# 250100020129x-HW-V3_0.net
KiCad netlist of a schematic drawn in EAGLE
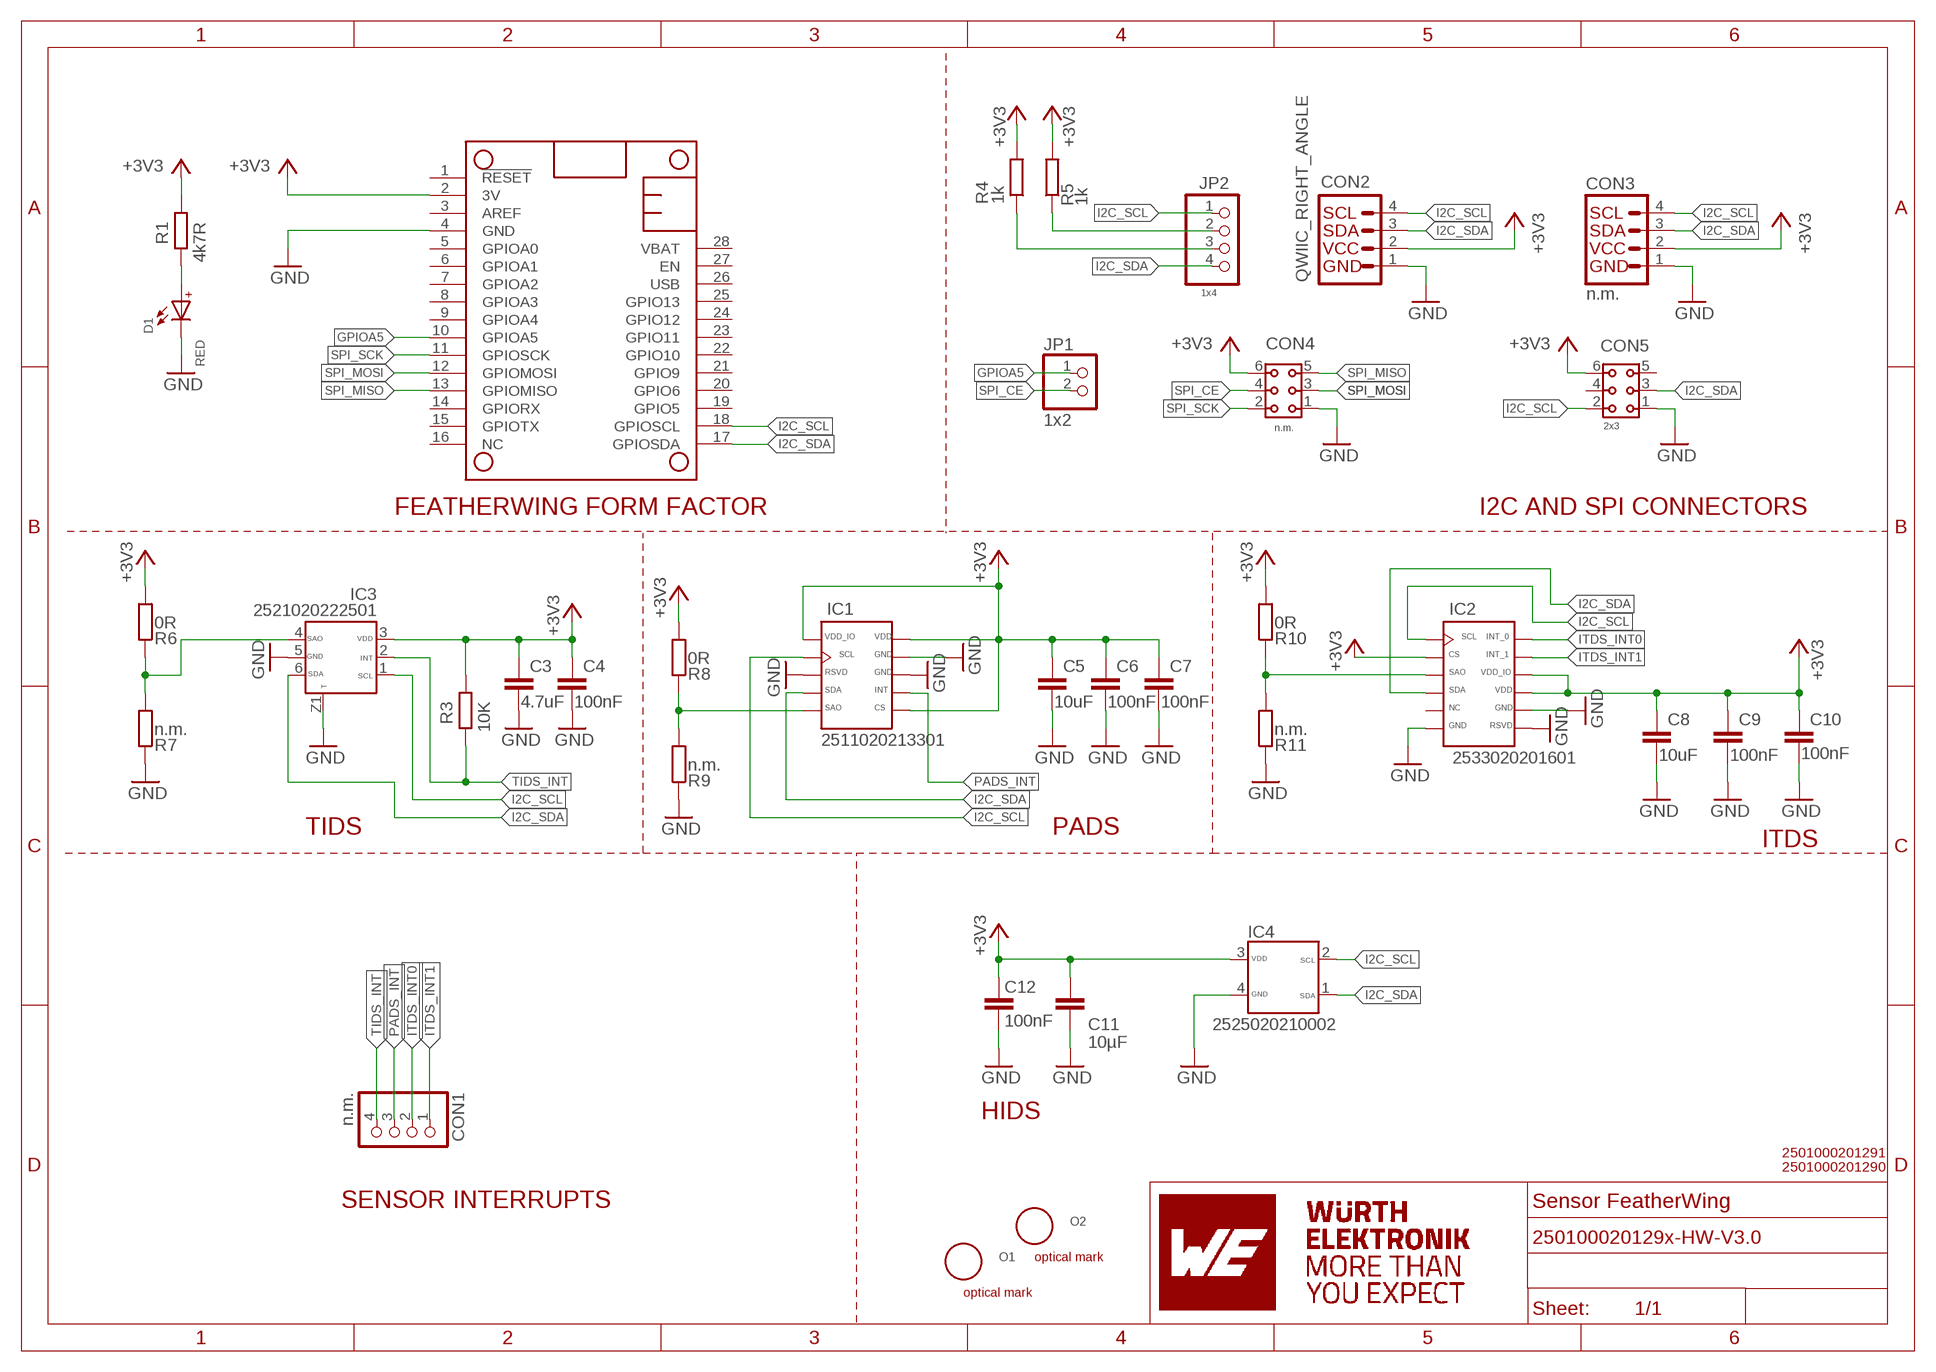
[diagram p0: schematic, sheet 1]

(export (version "E")
  (design (tool "Eeschema 10.0.6"))
  (components
    (comp (ref "C3")
      (value "4.7uF")
      (footprint "eagle-import:C0402_IPC")
      (fields (field (name "MANUFACTURER") "Würth Elektronik"))
      (libsource (lib "eagle-import") (part "C0402_IPC4.7UF"))
    )
    (comp (ref "C4")
      (value "100nF")
      (footprint "eagle-import:C0402_IPC")
      (fields (field (name "MANUFACTURER") "Würth Elektronik"))
      (libsource (lib "eagle-import") (part "C0402_IPC100NF"))
    )
    (comp (ref "C5")
      (value "10uF")
      (footprint "eagle-import:C0402_IPC")
      (fields (field (name "MANUFACTURER") "Würth Elektronik"))
      (libsource (lib "eagle-import") (part "C0402_IPC10UF"))
    )
    (comp (ref "C6")
      (value "100nF")
      (footprint "eagle-import:C0402_IPC")
      (fields (field (name "MANUFACTURER") "Würth Elektronik"))
      (libsource (lib "eagle-import") (part "C0402_IPC100NF"))
    )
    (comp (ref "C7")
      (value "100nF")
      (footprint "eagle-import:C0402_IPC")
      (fields (field (name "MANUFACTURER") "Würth Elektronik"))
      (libsource (lib "eagle-import") (part "C0402_IPC100NF"))
    )
    (comp (ref "C8")
      (value "10uF")
      (footprint "eagle-import:C0402_IPC")
      (fields (field (name "MANUFACTURER") "Würth Elektronik"))
      (libsource (lib "eagle-import") (part "C0402_IPC10UF"))
    )
    (comp (ref "C9")
      (value "100nF")
      (footprint "eagle-import:C0402_IPC")
      (fields (field (name "MANUFACTURER") "Würth Elektronik"))
      (libsource (lib "eagle-import") (part "C0402_IPC100NF"))
    )
    (comp (ref "C10")
      (value "100nF")
      (footprint "eagle-import:C0402_IPC")
      (fields (field (name "MANUFACTURER") "Würth Elektronik"))
      (libsource (lib "eagle-import") (part "C0402_IPC100NF"))
    )
    (comp (ref "C11")
      (value "10µF")
      (footprint "eagle-import:C0402_IPC")
      (fields (field (name "MANUFACTURER") "Würth Elektronik"))
      (libsource (lib "eagle-import") (part "C0402_IPC10UF"))
    )
    (comp (ref "C12")
      (value "100nF")
      (footprint "eagle-import:C0402_IPC")
      (fields (field (name "MANUFACTURER") "Würth Elektronik"))
      (libsource (lib "eagle-import") (part "C0402_IPC100NF"))
    )
    (comp (ref "CON1")
      (value "n.m.")
      (footprint "eagle-import:1X04_R")
      (fields (field (name "MANUFACTURER") "Würth Elektronik"))
      (libsource (lib "eagle-import") (part "PINHD-1X4/R"))
    )
    (comp (ref "CON2")
      (value "QWIIC_RIGHT_ANGLE")
      (footprint "eagle-import:JST04_1MM_RA")
      (fields (field (name "MANUFACTURER") "JST"))
      (libsource (lib "eagle-import") (part "QWIIC_CONNECTORJS-1MM"))
    )
    (comp (ref "CON3")
      (value "n.m.")
      (footprint "eagle-import:JST04_1MM_RA")
      (fields (field (name "MANUFACTURER") "JST"))
      (libsource (lib "eagle-import") (part "QWIIC_CONNECTORJS-1MM"))
    )
    (comp (ref "CON4")
      (value "n.m.")
      (footprint "eagle-import:613006243121")
      (fields (field (name "MANUFACTURER") "Würth Elektronik") (field (name "COMMENT") "Stick out of PCB"))
      (libsource (lib "eagle-import") (part "6130XX243121_613006243121"))
    )
    (comp (ref "CON5")
      (value "2x3")
      (footprint "eagle-import:613006243121")
      (fields (field (name "MANUFACTURER") "Würth Elektronik") (field (name "COMMENT") "Stick out of PCB"))
      (libsource (lib "eagle-import") (part "6130XX243121_613006243121"))
    )
    (comp (ref "D1")
      (value "RED")
      (footprint "eagle-import:WL-SMSW_1204_A")
      (fields (field (name "MANUFACTURER") "Würth Elektronik"))
      (libsource (lib "eagle-import") (part "WL-SMSW_1204_155124VS73200"))
    )
    (comp (ref "IC1")
      (value "2511020213301")
      (footprint "eagle-import:WSEN-PADS_2511020213301")
      (fields (field (name "MANUFACTURER") "Würth Elektronik"))
      (libsource (lib "eagle-import") (part "WSEN-PADS_2511020213301"))
    )
    (comp (ref "IC2")
      (value "2533020201601")
      (footprint "eagle-import:WSEN-ITDS_2533020201601")
      (fields (field (name "MANUFACTURER") "Würth Elektronik"))
      (libsource (lib "eagle-import") (part "WSEN-ITDS_2533020201601"))
    )
    (comp (ref "IC3")
      (value "2521020222501")
      (footprint "eagle-import:WSEN-TIDS_2521020222501")
      (fields (field (name "MANUFACTURER") "Würth Elektronik"))
      (libsource (lib "eagle-import") (part "WSEN-TIDS_2521020222501"))
    )
    (comp (ref "IC4")
      (value "2525020210002")
      (footprint "eagle-import:WSEN-HIDS_2525020210002")
      (fields (field (name "MANUFACTURER") "Würth Elektronik"))
      (libsource (lib "eagle-import") (part "WSEN-HIDS_2525020210002"))
    )
    (comp (ref "JP1")
      (value "1x2")
      (footprint "eagle-import:1X02_R")
      (fields (field (name "MANUFACTURER") "Würth Elektronik"))
      (libsource (lib "eagle-import") (part "PINHD-1X2/R"))
    )
    (comp (ref "JP2")
      (value "1x4")
      (footprint "eagle-import:1X04_R")
      (fields (field (name "COMMENT") "2xJumper, 1-2, 3-4") (field (name "MANUFACTURER") "Würth Elektronik"))
      (libsource (lib "eagle-import") (part "PINHD-1X4/R"))
    )
    (comp (ref "MS1")
      (value "FEATHERWING")
      (footprint "eagle-import:FEATHERWING")
      (fields
        (field (name "COMMENT") "header: 1 x 12 & 1 x 16, stackup, pins clean")
        (field (name "MANUFACTURER") "Adafruit")
      )
      (libsource (lib "eagle-import") (part "FEATHERWING"))
    )
    (comp (ref "O1")
      (value "OPT_MARKE")
      (footprint "eagle-import:OPTISCHE_MARKE")
      (libsource (lib "eagle-import") (part "OPT_MARKE"))
    )
    (comp (ref "O2")
      (value "OPT_MARKE")
      (footprint "eagle-import:OPTISCHE_MARKE")
      (libsource (lib "eagle-import") (part "OPT_MARKE"))
    )
    (comp (ref "R1")
      (value "4k7R")
      (footprint "eagle-import:R0402_IPC")
      (fields (field (name "MANUFACTURER") "Yageo"))
      (libsource (lib "eagle-import") (part "R0402_IPC4K7"))
    )
    (comp (ref "R3")
      (value "10K")
      (footprint "eagle-import:R0402_IPC")
      (fields (field (name "MANUFACTURER") "Yageo"))
      (libsource (lib "eagle-import") (part "R0402_IPC10KR"))
    )
    (comp (ref "R4")
      (value "1k")
      (footprint "eagle-import:R0402_IPC")
      (fields (field (name "MANUFACTURER") "Yageo"))
      (libsource (lib "eagle-import") (part "R0402_IPC1K"))
    )
    (comp (ref "R5")
      (value "1k")
      (footprint "eagle-import:R0402_IPC")
      (fields (field (name "MANUFACTURER") "Yageo"))
      (libsource (lib "eagle-import") (part "R0402_IPC1K"))
    )
    (comp (ref "R6")
      (value "0R")
      (footprint "eagle-import:R0402_IPC")
      (fields (field (name "MANUFACTURER") "Yageo"))
      (libsource (lib "eagle-import") (part "R0402_IPC0R"))
    )
    (comp (ref "R7")
      (value "n.m.")
      (footprint "eagle-import:R0402_IPC")
      (fields (field (name "MANUFACTURER") "Yageo"))
      (libsource (lib "eagle-import") (part "R0402_IPC"))
    )
    (comp (ref "R8")
      (value "0R")
      (footprint "eagle-import:R0402_IPC")
      (fields (field (name "MANUFACTURER") "Yageo"))
      (libsource (lib "eagle-import") (part "R0402_IPC0R"))
    )
    (comp (ref "R9")
      (value "n.m.")
      (footprint "eagle-import:R0402_IPC")
      (fields (field (name "MANUFACTURER") "Yageo"))
      (libsource (lib "eagle-import") (part "R0402_IPC"))
    )
    (comp (ref "R10")
      (value "0R")
      (footprint "eagle-import:R0402_IPC")
      (fields (field (name "MANUFACTURER") "Yageo"))
      (libsource (lib "eagle-import") (part "R0402_IPC0R"))
    )
    (comp (ref "R11")
      (value "n.m.")
      (footprint "eagle-import:R0402_IPC")
      (fields (field (name "MANUFACTURER") "Yageo"))
      (libsource (lib "eagle-import") (part "R0402_IPC"))
    )
  )
  (nets
    (net (code "1") (name "+3V3") (class "Default")
      (node (ref "C10") (pin "1") (pinfunction "1_1") (pintype "passive"))
      (node (ref "C11") (pin "2") (pinfunction "2_2") (pintype "passive"))
      (node (ref "C12") (pin "2") (pinfunction "2_2") (pintype "passive"))
      (node (ref "C3") (pin "1") (pinfunction "1_1") (pintype "passive"))
      (node (ref "C4") (pin "1") (pinfunction "1_1") (pintype "passive"))
      (node (ref "C5") (pin "1") (pinfunction "1_1") (pintype "passive"))
      (node (ref "C6") (pin "1") (pinfunction "1_1") (pintype "passive"))
      (node (ref "C7") (pin "1") (pinfunction "1_1") (pintype "passive"))
      (node (ref "C8") (pin "1") (pinfunction "1_1") (pintype "passive"))
      (node (ref "C9") (pin "1") (pinfunction "1_1") (pintype "passive"))
      (node (ref "CON2") (pin "2") (pinfunction "2_2") (pintype "power_in"))
      (node (ref "CON3") (pin "2") (pinfunction "2_2") (pintype "power_in"))
      (node (ref "CON4") (pin "6") (pinfunction "6_6") (pintype "passive"))
      (node (ref "CON5") (pin "6") (pinfunction "6_6") (pintype "passive"))
      (node (ref "IC1") (pin "1") (pinfunction "VDD_IO_1") (pintype "power_in"))
      (node (ref "IC1") (pin "10") (pinfunction "VDD_10") (pintype "power_in"))
      (node (ref "IC1") (pin "6") (pinfunction "CS_6") (pintype "input"))
      (node (ref "IC2") (pin "10") (pinfunction "VDD_IO_10") (pintype "power_in"))
      (node (ref "IC2") (pin "2") (pinfunction "CS_2") (pintype "input"))
      (node (ref "IC2") (pin "9") (pinfunction "VDD_9") (pintype "power_in"))
      (node (ref "IC3") (pin "3") (pinfunction "VDD_3") (pintype "power_in"))
      (node (ref "IC4") (pin "3") (pinfunction "VDD_3") (pintype "power_in"))
      (node (ref "MS1") (pin "2") (pinfunction "3V_2") (pintype "power_in"))
      (node (ref "R1") (pin "2") (pinfunction "2_2") (pintype "passive"))
      (node (ref "R10") (pin "2") (pinfunction "2_2") (pintype "passive"))
      (node (ref "R3") (pin "2") (pinfunction "2_2") (pintype "passive"))
      (node (ref "R4") (pin "2") (pinfunction "2_2") (pintype "passive"))
      (node (ref "R5") (pin "2") (pinfunction "2_2") (pintype "passive"))
      (node (ref "R6") (pin "2") (pinfunction "2_2") (pintype "passive"))
      (node (ref "R8") (pin "2") (pinfunction "2_2") (pintype "passive"))
    )
    (net (code "2") (name "/USB") (class "Default")
      (node (ref "MS1") (pin "26") (pinfunction "USB_26") (pintype "power_in"))
    )
    (net (code "3") (name "/VBAT") (class "Default")
      (node (ref "MS1") (pin "28") (pinfunction "VBAT_28") (pintype "power_in"))
    )
    (net (code "4") (name "GND") (class "Default")
      (node (ref "C10") (pin "2") (pinfunction "2_2") (pintype "passive"))
      (node (ref "C11") (pin "1") (pinfunction "1_1") (pintype "passive"))
      (node (ref "C12") (pin "1") (pinfunction "1_1") (pintype "passive"))
      (node (ref "C3") (pin "2") (pinfunction "2_2") (pintype "passive"))
      (node (ref "C4") (pin "2") (pinfunction "2_2") (pintype "passive"))
      (node (ref "C5") (pin "2") (pinfunction "2_2") (pintype "passive"))
      (node (ref "C6") (pin "2") (pinfunction "2_2") (pintype "passive"))
      (node (ref "C7") (pin "2") (pinfunction "2_2") (pintype "passive"))
      (node (ref "C8") (pin "2") (pinfunction "2_2") (pintype "passive"))
      (node (ref "C9") (pin "2") (pinfunction "2_2") (pintype "passive"))
      (node (ref "CON2") (pin "1") (pinfunction "1_1") (pintype "power_in"))
      (node (ref "CON3") (pin "1") (pinfunction "1_1") (pintype "power_in"))
      (node (ref "CON4") (pin "1") (pinfunction "1_1") (pintype "passive"))
      (node (ref "CON5") (pin "1") (pinfunction "1_1") (pintype "passive"))
      (node (ref "D1") (pin "1") (pinfunction "-_1") (pintype "passive"))
      (node (ref "IC1") (pin "3") (pinfunction "RSVD_3") (pintype "bidirectional"))
      (node (ref "IC1") (pin "8") (pinfunction "GND_8") (pintype "power_in"))
      (node (ref "IC1") (pin "9") (pinfunction "GND_9") (pintype "power_in"))
      (node (ref "IC2") (pin "6") (pinfunction "GND_6") (pintype "power_in"))
      (node (ref "IC2") (pin "7") (pinfunction "RSVD_7") (pintype "bidirectional"))
      (node (ref "IC2") (pin "8") (pinfunction "GND_8") (pintype "power_in"))
      (node (ref "IC3") (pin "5") (pinfunction "GND_5") (pintype "power_in"))
      (node (ref "IC3") (pin "Z1") (pinfunction "P$1_Z1") (pintype "bidirectional"))
      (node (ref "IC4") (pin "4") (pinfunction "GND_4") (pintype "power_in"))
      (node (ref "MS1") (pin "4") (pinfunction "GND_4") (pintype "power_in"))
      (node (ref "R11") (pin "1") (pinfunction "1_1") (pintype "passive"))
      (node (ref "R7") (pin "1") (pinfunction "1_1") (pintype "passive"))
      (node (ref "R9") (pin "1") (pinfunction "1_1") (pintype "passive"))
    )
    (net (code "5") (name "GPIOA5") (class "Default")
      (node (ref "JP1") (pin "1") (pinfunction "1_1") (pintype "passive"))
      (node (ref "MS1") (pin "10") (pinfunction "GPIOA5_10") (pintype "bidirectional"))
    )
    (net (code "6") (name "I2C_SCL") (class "Default")
      (node (ref "CON2") (pin "4") (pinfunction "4_4") (pintype "passive"))
      (node (ref "CON3") (pin "4") (pinfunction "4_4") (pintype "passive"))
      (node (ref "CON5") (pin "2") (pinfunction "2_2") (pintype "passive"))
      (node (ref "IC1") (pin "2") (pinfunction "SCL_2") (pintype "input"))
      (node (ref "IC2") (pin "1") (pinfunction "SCL_1") (pintype "input"))
      (node (ref "IC3") (pin "1") (pinfunction "SCL_1") (pintype "bidirectional"))
      (node (ref "IC4") (pin "2") (pinfunction "SCL_2") (pintype "bidirectional"))
      (node (ref "JP2") (pin "1") (pinfunction "1_1") (pintype "passive"))
      (node (ref "MS1") (pin "18") (pinfunction "GPIOSCL_18") (pintype "bidirectional"))
    )
    (net (code "7") (name "I2C_SDA") (class "Default")
      (node (ref "CON2") (pin "3") (pinfunction "3_3") (pintype "passive"))
      (node (ref "CON3") (pin "3") (pinfunction "3_3") (pintype "passive"))
      (node (ref "CON5") (pin "3") (pinfunction "3_3") (pintype "passive"))
      (node (ref "IC1") (pin "4") (pinfunction "SDA_4") (pintype "bidirectional"))
      (node (ref "IC2") (pin "4") (pinfunction "SDA_4") (pintype "bidirectional"))
      (node (ref "IC3") (pin "6") (pinfunction "SDA_6") (pintype "bidirectional"))
      (node (ref "IC4") (pin "1") (pinfunction "SDA_1") (pintype "bidirectional"))
      (node (ref "JP2") (pin "4") (pinfunction "4_4") (pintype "passive"))
      (node (ref "MS1") (pin "17") (pinfunction "GPIOSDA_17") (pintype "bidirectional"))
    )
    (net (code "8") (name "ITDS_INT0") (class "Default")
      (node (ref "CON1") (pin "2") (pinfunction "2_2") (pintype "passive"))
      (node (ref "IC2") (pin "12") (pinfunction "INT_0_12") (pintype "output"))
    )
    (net (code "9") (name "ITDS_INT1") (class "Default")
      (node (ref "CON1") (pin "1") (pinfunction "1_1") (pintype "passive"))
      (node (ref "IC2") (pin "11") (pinfunction "INT_1_11") (pintype "bidirectional"))
    )
    (net (code "10") (name "Net-(D1-+)") (class "Default")
      (node (ref "D1") (pin "2") (pinfunction "+_2") (pintype "passive"))
      (node (ref "R1") (pin "1") (pinfunction "1_1") (pintype "passive"))
    )
    (net (code "11") (name "Net-(IC1-SAO)") (class "Default")
      (node (ref "IC1") (pin "5") (pinfunction "SAO_5") (pintype "bidirectional"))
      (node (ref "R8") (pin "1") (pinfunction "1_1") (pintype "passive"))
      (node (ref "R9") (pin "2") (pinfunction "2_2") (pintype "passive"))
    )
    (net (code "12") (name "Net-(IC2-SAO)") (class "Default")
      (node (ref "IC2") (pin "3") (pinfunction "SAO_3") (pintype "bidirectional"))
      (node (ref "R10") (pin "1") (pinfunction "1_1") (pintype "passive"))
      (node (ref "R11") (pin "2") (pinfunction "2_2") (pintype "passive"))
    )
    (net (code "13") (name "Net-(IC3-SAO)") (class "Default")
      (node (ref "IC3") (pin "4") (pinfunction "SAO_4") (pintype "bidirectional"))
      (node (ref "R6") (pin "1") (pinfunction "1_1") (pintype "passive"))
      (node (ref "R7") (pin "2") (pinfunction "2_2") (pintype "passive"))
    )
    (net (code "14") (name "Net-(JP2-Pad2)") (class "Default")
      (node (ref "JP2") (pin "2") (pinfunction "2_2") (pintype "passive"))
      (node (ref "R5") (pin "1") (pinfunction "1_1") (pintype "passive"))
    )
    (net (code "15") (name "Net-(JP2-Pad3)") (class "Default")
      (node (ref "JP2") (pin "3") (pinfunction "3_3") (pintype "passive"))
      (node (ref "R4") (pin "1") (pinfunction "1_1") (pintype "passive"))
    )
    (net (code "16") (name "PADS_INT") (class "Default")
      (node (ref "CON1") (pin "3") (pinfunction "3_3") (pintype "passive"))
      (node (ref "IC1") (pin "7") (pinfunction "INT_7") (pintype "output"))
    )
    (net (code "17") (name "SPI_CE") (class "Default")
      (node (ref "CON4") (pin "4") (pinfunction "4_4") (pintype "passive"))
      (node (ref "JP1") (pin "2") (pinfunction "2_2") (pintype "passive"))
    )
    (net (code "18") (name "SPI_MISO") (class "Default")
      (node (ref "CON4") (pin "5") (pinfunction "5_5") (pintype "passive"))
      (node (ref "MS1") (pin "13") (pinfunction "GPIOMISO_13") (pintype "bidirectional"))
    )
    (net (code "19") (name "SPI_MOSI") (class "Default")
      (node (ref "CON4") (pin "3") (pinfunction "3_3") (pintype "passive"))
      (node (ref "MS1") (pin "12") (pinfunction "GPIOMOSI_12") (pintype "bidirectional"))
    )
    (net (code "20") (name "SPI_SCK") (class "Default")
      (node (ref "CON4") (pin "2") (pinfunction "2_2") (pintype "passive"))
      (node (ref "MS1") (pin "11") (pinfunction "GPIOSCK_11") (pintype "bidirectional"))
    )
    (net (code "21") (name "TIDS_INT") (class "Default")
      (node (ref "CON1") (pin "4") (pinfunction "4_4") (pintype "passive"))
      (node (ref "IC3") (pin "2") (pinfunction "INT_2") (pintype "bidirectional"))
      (node (ref "R3") (pin "1") (pinfunction "1_1") (pintype "passive"))
    )
    (net (code "22") (name "unconnected-(CON5-Pad4)") (class "Default")
      (node (ref "CON5") (pin "4") (pinfunction "4_4") (pintype "passive"))
    )
    (net (code "23") (name "unconnected-(CON5-Pad5)") (class "Default")
      (node (ref "CON5") (pin "5") (pinfunction "5_5") (pintype "passive"))
    )
    (net (code "24") (name "unconnected-(IC2-NC-Pad5)") (class "Default")
      (node (ref "IC2") (pin "5") (pinfunction "NC_5") (pintype "no_connect"))
    )
    (net (code "25") (name "unconnected-(MS1-AREF-Pad3)") (class "Default")
      (node (ref "MS1") (pin "3") (pinfunction "AREF_3") (pintype "passive"))
    )
    (net (code "26") (name "unconnected-(MS1-EN-Pad27)") (class "Default")
      (node (ref "MS1") (pin "27") (pinfunction "EN_27") (pintype "passive"))
    )
    (net (code "27") (name "unconnected-(MS1-GPIO5-Pad19)") (class "Default")
      (node (ref "MS1") (pin "19") (pinfunction "GPIO5_19") (pintype "bidirectional"))
    )
    (net (code "28") (name "unconnected-(MS1-GPIO6-Pad20)") (class "Default")
      (node (ref "MS1") (pin "20") (pinfunction "GPIO6_20") (pintype "bidirectional"))
    )
    (net (code "29") (name "unconnected-(MS1-GPIO9-Pad21)") (class "Default")
      (node (ref "MS1") (pin "21") (pinfunction "GPIO9_21") (pintype "bidirectional"))
    )
    (net (code "30") (name "unconnected-(MS1-GPIO10-Pad22)") (class "Default")
      (node (ref "MS1") (pin "22") (pinfunction "GPIO10_22") (pintype "bidirectional"))
    )
    (net (code "31") (name "unconnected-(MS1-GPIO11-Pad23)") (class "Default")
      (node (ref "MS1") (pin "23") (pinfunction "GPIO11_23") (pintype "bidirectional"))
    )
    (net (code "32") (name "unconnected-(MS1-GPIO12-Pad24)") (class "Default")
      (node (ref "MS1") (pin "24") (pinfunction "GPIO12_24") (pintype "bidirectional"))
    )
    (net (code "33") (name "unconnected-(MS1-GPIO13-Pad25)") (class "Default")
      (node (ref "MS1") (pin "25") (pinfunction "GPIO13_25") (pintype "bidirectional"))
    )
    (net (code "34") (name "unconnected-(MS1-GPIOA0-Pad5)") (class "Default")
      (node (ref "MS1") (pin "5") (pinfunction "GPIOA0_5") (pintype "bidirectional"))
    )
    (net (code "35") (name "unconnected-(MS1-GPIOA1-Pad6)") (class "Default")
      (node (ref "MS1") (pin "6") (pinfunction "GPIOA1_6") (pintype "bidirectional"))
    )
    (net (code "36") (name "unconnected-(MS1-GPIOA2-Pad7)") (class "Default")
      (node (ref "MS1") (pin "7") (pinfunction "GPIOA2_7") (pintype "bidirectional"))
    )
    (net (code "37") (name "unconnected-(MS1-GPIOA3-Pad8)") (class "Default")
      (node (ref "MS1") (pin "8") (pinfunction "GPIOA3_8") (pintype "bidirectional"))
    )
    (net (code "38") (name "unconnected-(MS1-GPIOA4-Pad9)") (class "Default")
      (node (ref "MS1") (pin "9") (pinfunction "GPIOA4_9") (pintype "bidirectional"))
    )
    (net (code "39") (name "unconnected-(MS1-GPIORX-Pad14)") (class "Default")
      (node (ref "MS1") (pin "14") (pinfunction "GPIORX_14") (pintype "bidirectional"))
    )
    (net (code "40") (name "unconnected-(MS1-GPIOTX-Pad15)") (class "Default")
      (node (ref "MS1") (pin "15") (pinfunction "GPIOTX_15") (pintype "bidirectional"))
    )
    (net (code "41") (name "unconnected-(MS1-NC-Pad16)") (class "Default")
      (node (ref "MS1") (pin "16") (pinfunction "NC_16") (pintype "passive"))
    )
    (net (code "42") (name "unconnected-(MS1-~{RESET}-Pad1)") (class "Default")
      (node (ref "MS1") (pin "1") (pinfunction "~{RESET}_1") (pintype "input"))
    )
  )
)
